# Ethernet_2.net
KiCad netlist of a schematic drawn in Altium Designer
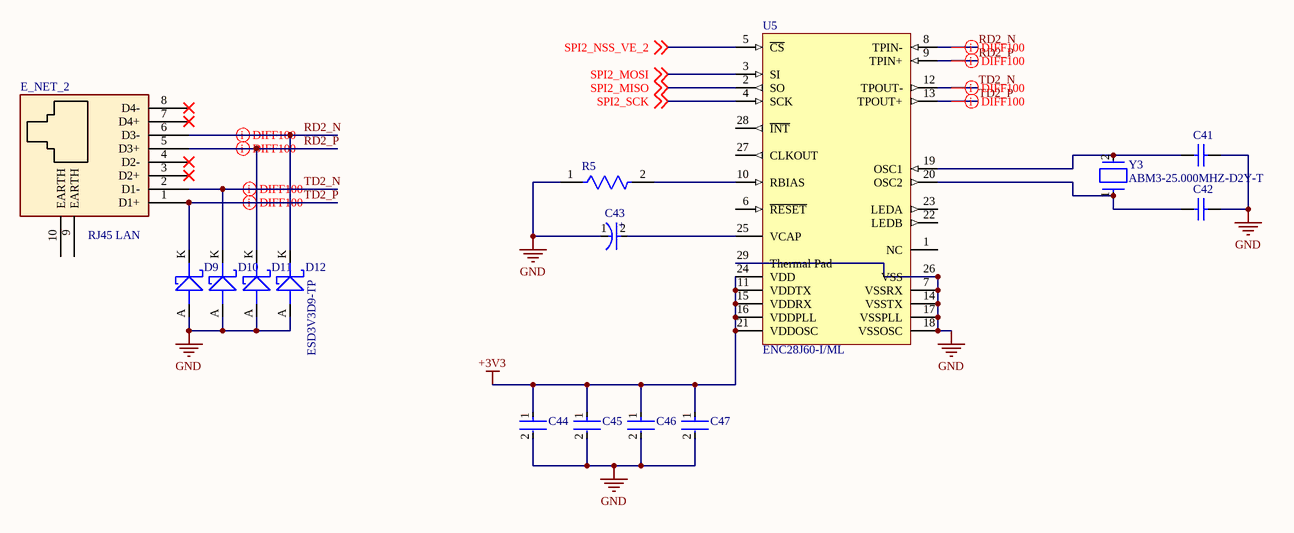
[diagram p0: Ethernet_2.SchDoc]

(export (version "E")
  (design (tool "Eeschema 10.0.6"))
  (components
    (comp (ref "C41")
      (value "CC0603JRNPO9BN180")
      (footprint "CAPC1608X90X40LL10T20")
      (description "Chip Capacitor, 18 pF, +/- 5%, 50 V, -55 to 125 degC, 0603 (1608 Metric), RoHS, Tape and Reel")
      (fields (field (name "TOLERANCE") "1%"))
      (libsource (lib "Altium Content Vault") (part "CAP-NP-2"))
    )
    (comp (ref "C42")
      (value "CC0603JRNPO9BN180")
      (footprint "CAPC1608X90X40LL10T20")
      (description "Chip Capacitor, 18 pF, +/- 5%, 50 V, -55 to 125 degC, 0603 (1608 Metric), RoHS, Tape and Reel")
      (fields (field (name "TOLERANCE") "1%"))
      (libsource (lib "Altium Content Vault") (part "CAP-NP-2"))
    )
    (comp (ref "C43")
      (value "593D106X9016A2TE3")
      (footprint "FP-593DA-MFG")
      (fields (field (name "TOLERANCE") "10%") (field (name "VOLTAGE") "16V"))
      (libsource (lib "Altium Content Vault") (part "a00bbbee19879c290e62620ae7e47b1"))
    )
    (comp (ref "C44")
      (value "C0402C104K8RACTU")
      (footprint "FP-C0402-BB-MFG")
      (description "CAP CER 0.1UF 10V X7R 0402")
      (fields
        (field (name "OCTOPART") "https://octopart.com/c0402c104k8ractu-kemet-106349")
        (field (name "TOLERANCE") "0.1")
      )
      (libsource (lib "Altium Content Vault") (part "b4654b650e69147ec39a6b967a45e02"))
    )
    (comp (ref "C45")
      (value "C0402C104K8RACTU")
      (footprint "FP-C0402-BB-MFG")
      (description "CAP CER 0.1UF 10V X7R 0402")
      (fields
        (field (name "OCTOPART") "https://octopart.com/c0402c104k8ractu-kemet-106349")
        (field (name "TOLERANCE") "0.1")
      )
      (libsource (lib "Altium Content Vault") (part "b4654b650e69147ec39a6b967a45e02"))
    )
    (comp (ref "C46")
      (value "C0402C104K8RACTU")
      (footprint "FP-C0402-BB-MFG")
      (description "CAP CER 0.1UF 10V X7R 0402")
      (fields
        (field (name "OCTOPART") "https://octopart.com/c0402c104k8ractu-kemet-106349")
        (field (name "TOLERANCE") "0.1")
      )
      (libsource (lib "Altium Content Vault") (part "b4654b650e69147ec39a6b967a45e02"))
    )
    (comp (ref "C47")
      (value "C0402C104K8RACTU")
      (footprint "FP-C0402-BB-MFG")
      (description "CAP CER 0.1UF 10V X7R 0402")
      (fields
        (field (name "OCTOPART") "https://octopart.com/c0402c104k8ractu-kemet-106349")
        (field (name "TOLERANCE") "0.1")
      )
      (libsource (lib "Altium Content Vault") (part "b4654b650e69147ec39a6b967a45e02"))
    )
    (comp (ref "D9")
      (value "ESD3V3D9-TP")
      (footprint "DIO_SOD-923")
      (description "8.8V Clamp 5A (8/20µs) Ipp Tvs Diode Surface Mount SOD-923")
      (fields (field (name "MANUFACTURER") "Micro Commercial Co"))
      (libsource (lib "ESTEEMPCBLIB") (part "DIO-T_3.3V-8.8V-SOD923"))
    )
    (comp (ref "D10")
      (value "ESD3V3D9-TP")
      (footprint "DIO_SOD-923")
      (description "8.8V Clamp 5A (8/20µs) Ipp Tvs Diode Surface Mount SOD-923")
      (fields (field (name "MANUFACTURER") "Micro Commercial Co"))
      (libsource (lib "ESTEEMPCBLIB") (part "DIO-T_3.3V-8.8V-SOD923"))
    )
    (comp (ref "D11")
      (value "ESD3V3D9-TP")
      (footprint "DIO_SOD-923")
      (description "8.8V Clamp 5A (8/20µs) Ipp Tvs Diode Surface Mount SOD-923")
      (fields (field (name "MANUFACTURER") "Micro Commercial Co"))
      (libsource (lib "ESTEEMPCBLIB") (part "DIO-T_3.3V-8.8V-SOD923"))
    )
    (comp (ref "D12")
      (value "ESD3V3D9-TP")
      (footprint "DIO_SOD-923")
      (description "8.8V Clamp 5A (8/20µs) Ipp Tvs Diode Surface Mount SOD-923")
      (fields (field (name "MANUFACTURER") "Micro Commercial Co"))
      (libsource (lib "ESTEEMPCBLIB") (part "DIO-T_3.3V-8.8V-SOD923"))
    )
    (comp (ref "E_NET_2")
      (value "RJ45 LAN")
      (footprint "CON10_P106_RJ45_TH_ST")
      (description "8 Pins, 2 Row 2.54mm Pitch, right angle Connector, male")
      (fields
        (field (name "MANUFACTURER") "Assmann")
        (field (name "MANUFACTURER PART NUMBER") "A-2004-2-4-LPS-N-R")
      )
      (libsource (lib "ESTEEMPCBLIB") (part "CON-SKT-RJ_8C8P-RA-TH"))
    )
    (comp (ref "R5")
      (value "ERJ-2RKF2001X")
      (footprint "FP-ERJ2RK-MFG")
      (description "RES SMD 2K OHM 1% 1/10W 0402")
      (fields (field (name "TOLERANCE") "1%"))
      (libsource (lib "Altium Content Vault") (part "1029c3af85768c4190bb7ad29bc67b5"))
    )
    (comp (ref "U5")
      (value "ENC28J60-I/ML")
      (footprint "QFN-ML28_M")
      (description "Stand-Alone Ethernet Controller with SPI Interface, 28-Pin QFN, Industrial Temperature")
      (libsource (lib "Altium Content Vault") (part "COM-ENET-ENC28J60-29"))
    )
    (comp (ref "Y3")
      (value "ABM3-25.000MHZ-D2Y-T")
      (footprint "FP-ABM3-MFG")
      (description "Crystal 25MHz ±20ppm 18pF SMD-2 5mm x 3.2mm")
      (fields (field (name "TOLERANCE") "20ppm"))
      (libsource (lib "Altium Content Vault") (part "c23a69dc6c9e2f18f2079038eb95dd1"))
    )
  )
  (nets
    (net (code "1") (name "+3V3") (class "Default")
      (node (ref "C44") (pin "1") (pinfunction "1_1") (pintype "passive"))
      (node (ref "C45") (pin "1") (pinfunction "1_1") (pintype "passive"))
      (node (ref "C46") (pin "1") (pinfunction "1_1") (pintype "passive"))
      (node (ref "C47") (pin "1") (pinfunction "1_1") (pintype "passive"))
      (node (ref "U5") (pin "11") (pinfunction "VDDTX_11") (pintype "power_in"))
      (node (ref "U5") (pin "15") (pinfunction "VDDRX_15") (pintype "power_in"))
      (node (ref "U5") (pin "16") (pinfunction "VDDPLL_16") (pintype "power_in"))
      (node (ref "U5") (pin "21") (pinfunction "VDDOSC_21") (pintype "power_in"))
      (node (ref "U5") (pin "24") (pinfunction "VDD_24") (pintype "power_in"))
    )
    (net (code "2") (name "/RD2_N") (class "Default")
      (node (ref "D12") (pin "K") (pinfunction "K_K") (pintype "passive"))
      (node (ref "E_NET_2") (pin "6") (pinfunction "D3-_6") (pintype "passive"))
      (node (ref "U5") (pin "8") (pinfunction "TPIN-_8") (pintype "input"))
    )
    (net (code "3") (name "/RD2_P") (class "Default")
      (node (ref "D11") (pin "K") (pinfunction "K_K") (pintype "passive"))
      (node (ref "E_NET_2") (pin "5") (pinfunction "D3+_5") (pintype "passive"))
      (node (ref "U5") (pin "9") (pinfunction "TPIN+_9") (pintype "input"))
    )
    (net (code "4") (name "/TD2_N") (class "Default")
      (node (ref "D10") (pin "K") (pinfunction "K_K") (pintype "passive"))
      (node (ref "E_NET_2") (pin "2") (pinfunction "D1-_2") (pintype "passive"))
      (node (ref "U5") (pin "12") (pinfunction "TPOUT-_12") (pintype "output"))
    )
    (net (code "5") (name "/TD2_P") (class "Default")
      (node (ref "D9") (pin "K") (pinfunction "K_K") (pintype "passive"))
      (node (ref "E_NET_2") (pin "1") (pinfunction "D1+_1") (pintype "passive"))
      (node (ref "U5") (pin "13") (pinfunction "TPOUT+_13") (pintype "output"))
    )
    (net (code "6") (name "GND") (class "Default")
      (node (ref "C41") (pin "1") (pinfunction "1_1") (pintype "passive"))
      (node (ref "C42") (pin "1") (pinfunction "1_1") (pintype "passive"))
      (node (ref "C43") (pin "1") (pinfunction "C_1") (pintype "passive"))
      (node (ref "C44") (pin "2") (pinfunction "2_2") (pintype "passive"))
      (node (ref "C45") (pin "2") (pinfunction "2_2") (pintype "passive"))
      (node (ref "C46") (pin "2") (pinfunction "2_2") (pintype "passive"))
      (node (ref "C47") (pin "2") (pinfunction "2_2") (pintype "passive"))
      (node (ref "D10") (pin "A") (pinfunction "A_A") (pintype "passive"))
      (node (ref "D11") (pin "A") (pinfunction "A_A") (pintype "passive"))
      (node (ref "D12") (pin "A") (pinfunction "A_A") (pintype "passive"))
      (node (ref "D9") (pin "A") (pinfunction "A_A") (pintype "passive"))
      (node (ref "R5") (pin "1") (pinfunction "1_1") (pintype "passive"))
      (node (ref "U5") (pin "14") (pinfunction "VSSTX_14") (pintype "power_in"))
      (node (ref "U5") (pin "17") (pinfunction "VSSPLL_17") (pintype "power_in"))
      (node (ref "U5") (pin "18") (pinfunction "VSSOSC_18") (pintype "power_in"))
      (node (ref "U5") (pin "26") (pinfunction "VSS_26") (pintype "power_in"))
      (node (ref "U5") (pin "29") (pinfunction "Thermal_Pad_29") (pintype "passive"))
      (node (ref "U5") (pin "7") (pinfunction "VSSRX_7") (pintype "power_in"))
    )
    (net (code "7") (name "Net-(C43-A)") (class "Default")
      (node (ref "C43") (pin "2") (pinfunction "A_2") (pintype "passive"))
      (node (ref "U5") (pin "25") (pinfunction "VCAP_25") (pintype "power_in"))
    )
    (net (code "8") (name "Net-(U5-OSC1)") (class "Default")
      (node (ref "C41") (pin "2") (pinfunction "2_2") (pintype "passive"))
      (node (ref "U5") (pin "19") (pinfunction "OSC1_19") (pintype "input"))
      (node (ref "Y3") (pin "2") (pinfunction "2_2") (pintype "passive"))
    )
    (net (code "9") (name "Net-(U5-OSC2)") (class "Default")
      (node (ref "C42") (pin "2") (pinfunction "2_2") (pintype "passive"))
      (node (ref "U5") (pin "20") (pinfunction "OSC2_20") (pintype "output"))
      (node (ref "Y3") (pin "1") (pinfunction "1_1") (pintype "passive"))
    )
    (net (code "10") (name "Net-(U5-RBIAS)") (class "Default")
      (node (ref "R5") (pin "2") (pinfunction "2_2") (pintype "passive"))
      (node (ref "U5") (pin "10") (pinfunction "RBIAS_10") (pintype "input"))
    )
    (net (code "11") (name "SPI2_MISO") (class "Default")
      (node (ref "U5") (pin "2") (pinfunction "SO_2") (pintype "output"))
    )
    (net (code "12") (name "SPI2_MOSI") (class "Default")
      (node (ref "U5") (pin "3") (pinfunction "SI_3") (pintype "input"))
    )
    (net (code "13") (name "SPI2_NSS_VE_2") (class "Default")
      (node (ref "U5") (pin "5") (pinfunction "~{CS}_5") (pintype "input"))
    )
    (net (code "14") (name "SPI2_SCK") (class "Default")
      (node (ref "U5") (pin "4") (pinfunction "SCK_4") (pintype "input"))
    )
    (net (code "15") (name "unconnected-(E_NET_2-D2+-Pad3)") (class "Default")
      (node (ref "E_NET_2") (pin "3") (pinfunction "D2+_3") (pintype "passive+no_connect"))
    )
    (net (code "16") (name "unconnected-(E_NET_2-D2--Pad4)") (class "Default")
      (node (ref "E_NET_2") (pin "4") (pinfunction "D2-_4") (pintype "passive+no_connect"))
    )
    (net (code "17") (name "unconnected-(E_NET_2-D4+-Pad7)") (class "Default")
      (node (ref "E_NET_2") (pin "7") (pinfunction "D4+_7") (pintype "passive+no_connect"))
    )
    (net (code "18") (name "unconnected-(E_NET_2-D4--Pad8)") (class "Default")
      (node (ref "E_NET_2") (pin "8") (pinfunction "D4-_8") (pintype "passive+no_connect"))
    )
    (net (code "19") (name "unconnected-(E_NET_2-EARTH-Pad9)") (class "Default")
      (node (ref "E_NET_2") (pin "9") (pinfunction "EARTH_9") (pintype "passive"))
    )
    (net (code "20") (name "unconnected-(E_NET_2-EARTH-Pad10)") (class "Default")
      (node (ref "E_NET_2") (pin "10") (pinfunction "EARTH_10") (pintype "passive"))
    )
    (net (code "21") (name "unconnected-(U5-CLKOUT-Pad27)") (class "Default")
      (node (ref "U5") (pin "27") (pinfunction "CLKOUT_27") (pintype "output"))
    )
    (net (code "22") (name "unconnected-(U5-LEDA-Pad23)") (class "Default")
      (node (ref "U5") (pin "23") (pinfunction "LEDA_23") (pintype "output"))
    )
    (net (code "23") (name "unconnected-(U5-LEDB-Pad22)") (class "Default")
      (node (ref "U5") (pin "22") (pinfunction "LEDB_22") (pintype "output"))
    )
    (net (code "24") (name "unconnected-(U5-NC-Pad1)") (class "Default")
      (node (ref "U5") (pin "1") (pinfunction "NC_1") (pintype "passive"))
    )
    (net (code "25") (name "unconnected-(U5-~{INT}-Pad28)") (class "Default")
      (node (ref "U5") (pin "28") (pinfunction "~{INT}_28") (pintype "output"))
    )
    (net (code "26") (name "unconnected-(U5-~{RESET}-Pad6)") (class "Default")
      (node (ref "U5") (pin "6") (pinfunction "~{RESET}_6") (pintype "input"))
    )
  )
)
